# MAC_ADC_v1_0.net
KiCad netlist of a schematic drawn in EAGLE
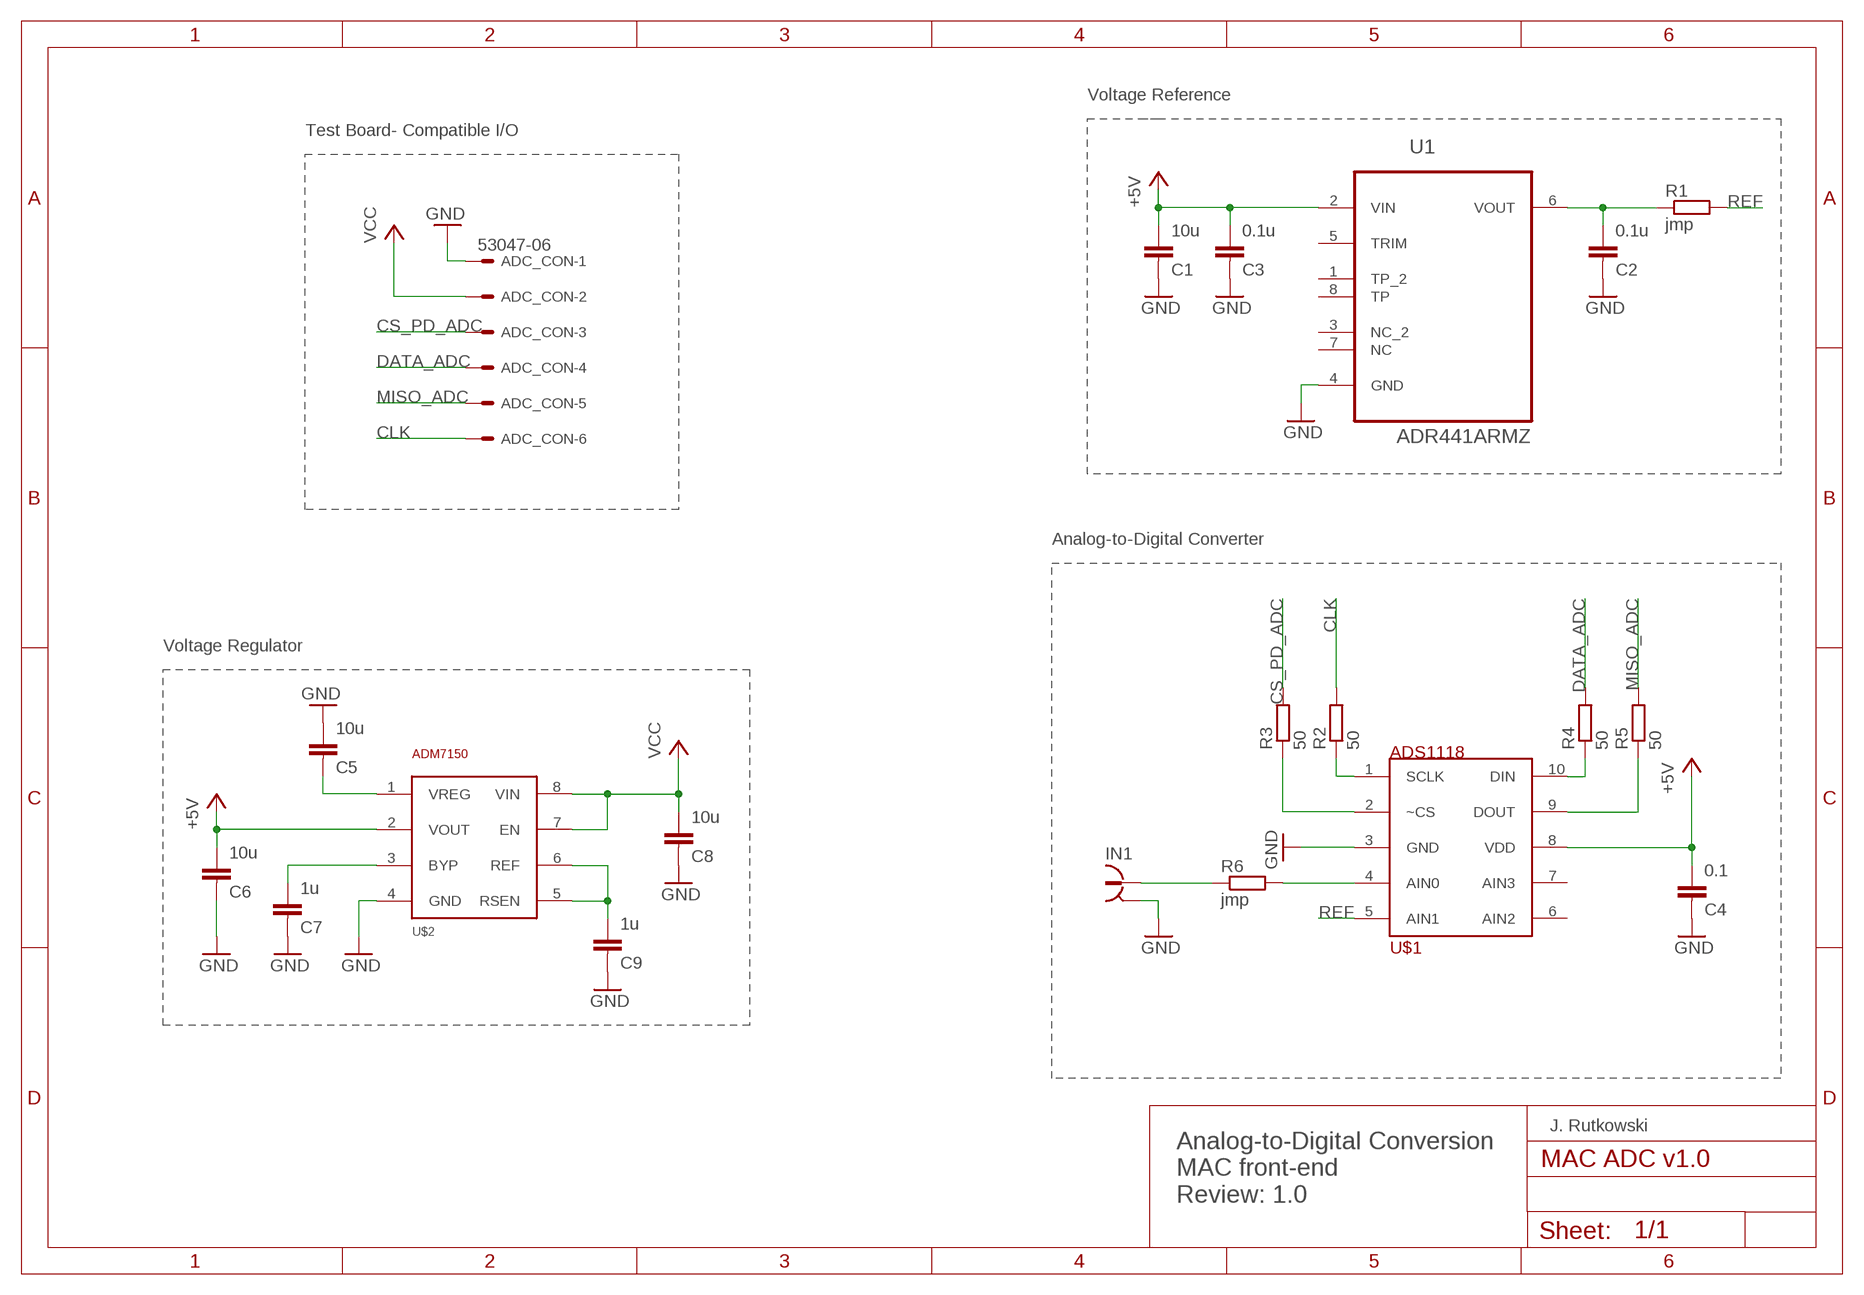
[diagram p0: schematic, sheet 1]

(export (version "E")
  (design (tool "Eeschema 10.0.6"))
  (components
    (comp (ref "ADC_CON")
      (value "53047-06")
      (footprint "eagle-import:53047-06")
      (fields (field (name "MPN") "53047-0610-C"))
      (libsource (lib "eagle-import") (part "53?-06047"))
    )
    (comp (ref "C1")
      (value "10u")
      (footprint "eagle-import:C0603K")
      (libsource (lib "eagle-import") (part "C-EUC0603K"))
    )
    (comp (ref "C2")
      (value "0.1u")
      (footprint "eagle-import:C0603K")
      (libsource (lib "eagle-import") (part "C-EUC0603K"))
    )
    (comp (ref "C3")
      (value "0.1u")
      (footprint "eagle-import:C0603K")
      (libsource (lib "eagle-import") (part "C-EUC0603K"))
    )
    (comp (ref "C4")
      (value "0.1")
      (footprint "eagle-import:C0603K")
      (libsource (lib "eagle-import") (part "C-EUC0603K"))
    )
    (comp (ref "C5")
      (value "10u")
      (footprint "eagle-import:C0603K")
      (libsource (lib "eagle-import") (part "C-EUC0603K"))
    )
    (comp (ref "C6")
      (value "10u")
      (footprint "eagle-import:C0603K")
      (libsource (lib "eagle-import") (part "C-EUC0603K"))
    )
    (comp (ref "C7")
      (value "1u")
      (footprint "eagle-import:C0603K")
      (libsource (lib "eagle-import") (part "C-EUC0603K"))
    )
    (comp (ref "C8")
      (value "10u")
      (footprint "eagle-import:C0603K")
      (libsource (lib "eagle-import") (part "C-EUC0603K"))
    )
    (comp (ref "C9")
      (value "1u")
      (footprint "eagle-import:C0603K")
      (libsource (lib "eagle-import") (part "C-EUC0603K"))
    )
    (comp (ref "IN1")
      (value "734120110")
      (footprint "eagle-import:734120110")
      (libsource (lib "eagle-import") (part "734120110"))
    )
    (comp (ref "R1")
      (value "jmp")
      (footprint "eagle-import:R0603")
      (libsource (lib "eagle-import") (part "R-EU_R0603"))
    )
    (comp (ref "R2")
      (value "50")
      (footprint "eagle-import:R0603")
      (libsource (lib "eagle-import") (part "R-EU_R0603"))
    )
    (comp (ref "R3")
      (value "50")
      (footprint "eagle-import:R0603")
      (libsource (lib "eagle-import") (part "R-EU_R0603"))
    )
    (comp (ref "R4")
      (value "50")
      (footprint "eagle-import:R0603")
      (libsource (lib "eagle-import") (part "R-EU_R0603"))
    )
    (comp (ref "R5")
      (value "50")
      (footprint "eagle-import:R0603")
      (libsource (lib "eagle-import") (part "R-EU_R0603"))
    )
    (comp (ref "R6")
      (value "jmp")
      (footprint "eagle-import:R0603")
      (libsource (lib "eagle-import") (part "R-EU_R0603"))
    )
    (comp (ref "U$1")
      (value "ADS1118IDGSR")
      (footprint "eagle-import:SOP50P490X110-10N")
      (libsource (lib "eagle-import") (part "ADS1118IDGSR"))
    )
    (comp (ref "U$2")
      (value "ADM7150")
      (footprint "eagle-import:SO8")
      (libsource (lib "eagle-import") (part "ADM7150"))
    )
    (comp (ref "U1")
      (value "ADR441ARMZ")
      (footprint "eagle-import:SOP65P490X110-8N")
      (libsource (lib "eagle-import") (part "ADR441ARMZ"))
    )
  )
  (nets
    (net (code "1") (name "+5V") (class "Default")
      (node (ref "C1") (pin "1") (pinfunction "1_1") (pintype "passive"))
      (node (ref "C3") (pin "1") (pinfunction "1_1") (pintype "passive"))
      (node (ref "C4") (pin "1") (pinfunction "1_1") (pintype "passive"))
      (node (ref "C6") (pin "1") (pinfunction "1_1") (pintype "passive"))
      (node (ref "U$1") (pin "8") (pinfunction "VDD_8") (pintype "bidirectional"))
      (node (ref "U$2") (pin "2") (pinfunction "VOUT_2") (pintype "bidirectional"))
      (node (ref "U1") (pin "2") (pinfunction "VIN_2") (pintype "input"))
    )
    (net (code "2") (name "/CLK") (class "Default")
      (node (ref "ADC_CON") (pin "6") (pinfunction "S_6") (pintype "passive"))
      (node (ref "R2") (pin "2") (pinfunction "2_2") (pintype "passive"))
    )
    (net (code "3") (name "/CS_PD_ADC") (class "Default")
      (node (ref "ADC_CON") (pin "3") (pinfunction "S_3") (pintype "passive"))
      (node (ref "R3") (pin "2") (pinfunction "2_2") (pintype "passive"))
    )
    (net (code "4") (name "/DATA_ADC") (class "Default")
      (node (ref "ADC_CON") (pin "4") (pinfunction "S_4") (pintype "passive"))
      (node (ref "R4") (pin "2") (pinfunction "2_2") (pintype "passive"))
    )
    (net (code "5") (name "/MISO_ADC") (class "Default")
      (node (ref "ADC_CON") (pin "5") (pinfunction "S_5") (pintype "passive"))
      (node (ref "R5") (pin "2") (pinfunction "2_2") (pintype "passive"))
    )
    (net (code "6") (name "/REF") (class "Default")
      (node (ref "R1") (pin "2") (pinfunction "2_2") (pintype "passive"))
      (node (ref "U$1") (pin "5") (pinfunction "AIN1_5") (pintype "bidirectional"))
    )
    (net (code "7") (name "GND") (class "Default")
      (node (ref "ADC_CON") (pin "1") (pinfunction "S_1") (pintype "passive"))
      (node (ref "C1") (pin "2") (pinfunction "2_2") (pintype "passive"))
      (node (ref "C2") (pin "2") (pinfunction "2_2") (pintype "passive"))
      (node (ref "C3") (pin "2") (pinfunction "2_2") (pintype "passive"))
      (node (ref "C4") (pin "2") (pinfunction "2_2") (pintype "passive"))
      (node (ref "C5") (pin "1") (pinfunction "1_1") (pintype "passive"))
      (node (ref "C6") (pin "2") (pinfunction "2_2") (pintype "passive"))
      (node (ref "C7") (pin "2") (pinfunction "2_2") (pintype "passive"))
      (node (ref "C8") (pin "2") (pinfunction "2_2") (pintype "passive"))
      (node (ref "C9") (pin "2") (pinfunction "2_2") (pintype "passive"))
      (node (ref "IN1") (pin "S@1") (pinfunction "2_S@1") (pintype "passive"))
      (node (ref "IN1") (pin "S@2") (pinfunction "2_S@2") (pintype "passive"))
      (node (ref "IN1") (pin "S@3") (pinfunction "2_S@3") (pintype "passive"))
      (node (ref "U$1") (pin "3") (pinfunction "GND_3") (pintype "bidirectional"))
      (node (ref "U$2") (pin "4") (pinfunction "GND_4") (pintype "bidirectional"))
      (node (ref "U1") (pin "4") (pinfunction "GND_4") (pintype "passive"))
    )
    (net (code "8") (name "Net-(IN1-Pad1)") (class "Default")
      (node (ref "IN1") (pin "1") (pinfunction "1_1") (pintype "passive"))
      (node (ref "R6") (pin "1") (pinfunction "1_1") (pintype "passive"))
    )
    (net (code "9") (name "Net-(U$1-AIN0)") (class "Default")
      (node (ref "R6") (pin "2") (pinfunction "2_2") (pintype "passive"))
      (node (ref "U$1") (pin "4") (pinfunction "AIN0_4") (pintype "bidirectional"))
    )
    (net (code "10") (name "Net-(U$1-DIN)") (class "Default")
      (node (ref "R4") (pin "1") (pinfunction "1_1") (pintype "passive"))
      (node (ref "U$1") (pin "10") (pinfunction "DIN_10") (pintype "bidirectional"))
    )
    (net (code "11") (name "Net-(U$1-DOUT)") (class "Default")
      (node (ref "R5") (pin "1") (pinfunction "1_1") (pintype "passive"))
      (node (ref "U$1") (pin "9") (pinfunction "DOUT_9") (pintype "bidirectional"))
    )
    (net (code "12") (name "Net-(U$1-SCLK)") (class "Default")
      (node (ref "R2") (pin "1") (pinfunction "1_1") (pintype "passive"))
      (node (ref "U$1") (pin "1") (pinfunction "SCLK_1") (pintype "bidirectional"))
    )
    (net (code "13") (name "Net-(U$1-~{CS})") (class "Default")
      (node (ref "R3") (pin "1") (pinfunction "1_1") (pintype "passive"))
      (node (ref "U$1") (pin "2") (pinfunction "~{CS}_2") (pintype "bidirectional"))
    )
    (net (code "14") (name "Net-(U$2-BYP)") (class "Default")
      (node (ref "C7") (pin "1") (pinfunction "1_1") (pintype "passive"))
      (node (ref "U$2") (pin "3") (pinfunction "BYP_3") (pintype "bidirectional"))
    )
    (net (code "15") (name "Net-(U$2-REF)") (class "Default")
      (node (ref "C9") (pin "1") (pinfunction "1_1") (pintype "passive"))
      (node (ref "U$2") (pin "5") (pinfunction "RSEN_5") (pintype "bidirectional"))
      (node (ref "U$2") (pin "6") (pinfunction "REF_6") (pintype "bidirectional"))
    )
    (net (code "16") (name "Net-(U$2-VREG)") (class "Default")
      (node (ref "C5") (pin "2") (pinfunction "2_2") (pintype "passive"))
      (node (ref "U$2") (pin "1") (pinfunction "VREG_1") (pintype "bidirectional"))
    )
    (net (code "17") (name "Net-(U1-VOUT)") (class "Default")
      (node (ref "C2") (pin "1") (pinfunction "1_1") (pintype "passive"))
      (node (ref "R1") (pin "1") (pinfunction "1_1") (pintype "passive"))
      (node (ref "U1") (pin "6") (pinfunction "VOUT_6") (pintype "output"))
    )
    (net (code "18") (name "VCC") (class "Default")
      (node (ref "ADC_CON") (pin "2") (pinfunction "S_2") (pintype "passive"))
      (node (ref "C8") (pin "1") (pinfunction "1_1") (pintype "passive"))
      (node (ref "U$2") (pin "7") (pinfunction "EN_7") (pintype "bidirectional"))
      (node (ref "U$2") (pin "8") (pinfunction "VIN_8") (pintype "bidirectional"))
    )
    (net (code "19") (name "unconnected-(U$1-AIN2-Pad6)") (class "Default")
      (node (ref "U$1") (pin "6") (pinfunction "AIN2_6") (pintype "bidirectional"))
    )
    (net (code "20") (name "unconnected-(U$1-AIN3-Pad7)") (class "Default")
      (node (ref "U$1") (pin "7") (pinfunction "AIN3_7") (pintype "bidirectional"))
    )
    (net (code "21") (name "unconnected-(U1-NC-Pad7)") (class "Default")
      (node (ref "U1") (pin "7") (pinfunction "NC_7") (pintype "no_connect"))
    )
    (net (code "22") (name "unconnected-(U1-NC_2-Pad3)") (class "Default")
      (node (ref "U1") (pin "3") (pinfunction "NC_2_3") (pintype "no_connect"))
    )
    (net (code "23") (name "unconnected-(U1-TP-Pad8)") (class "Default")
      (node (ref "U1") (pin "8") (pinfunction "TP_8") (pintype "passive"))
    )
    (net (code "24") (name "unconnected-(U1-TP_2-Pad1)") (class "Default")
      (node (ref "U1") (pin "1") (pinfunction "TP_2_1") (pintype "passive"))
    )
    (net (code "25") (name "unconnected-(U1-TRIM-Pad5)") (class "Default")
      (node (ref "U1") (pin "5") (pinfunction "TRIM_5") (pintype "passive"))
    )
  )
)
